# design.net
KiCad netlist of a schematic drawn in Altium Designer
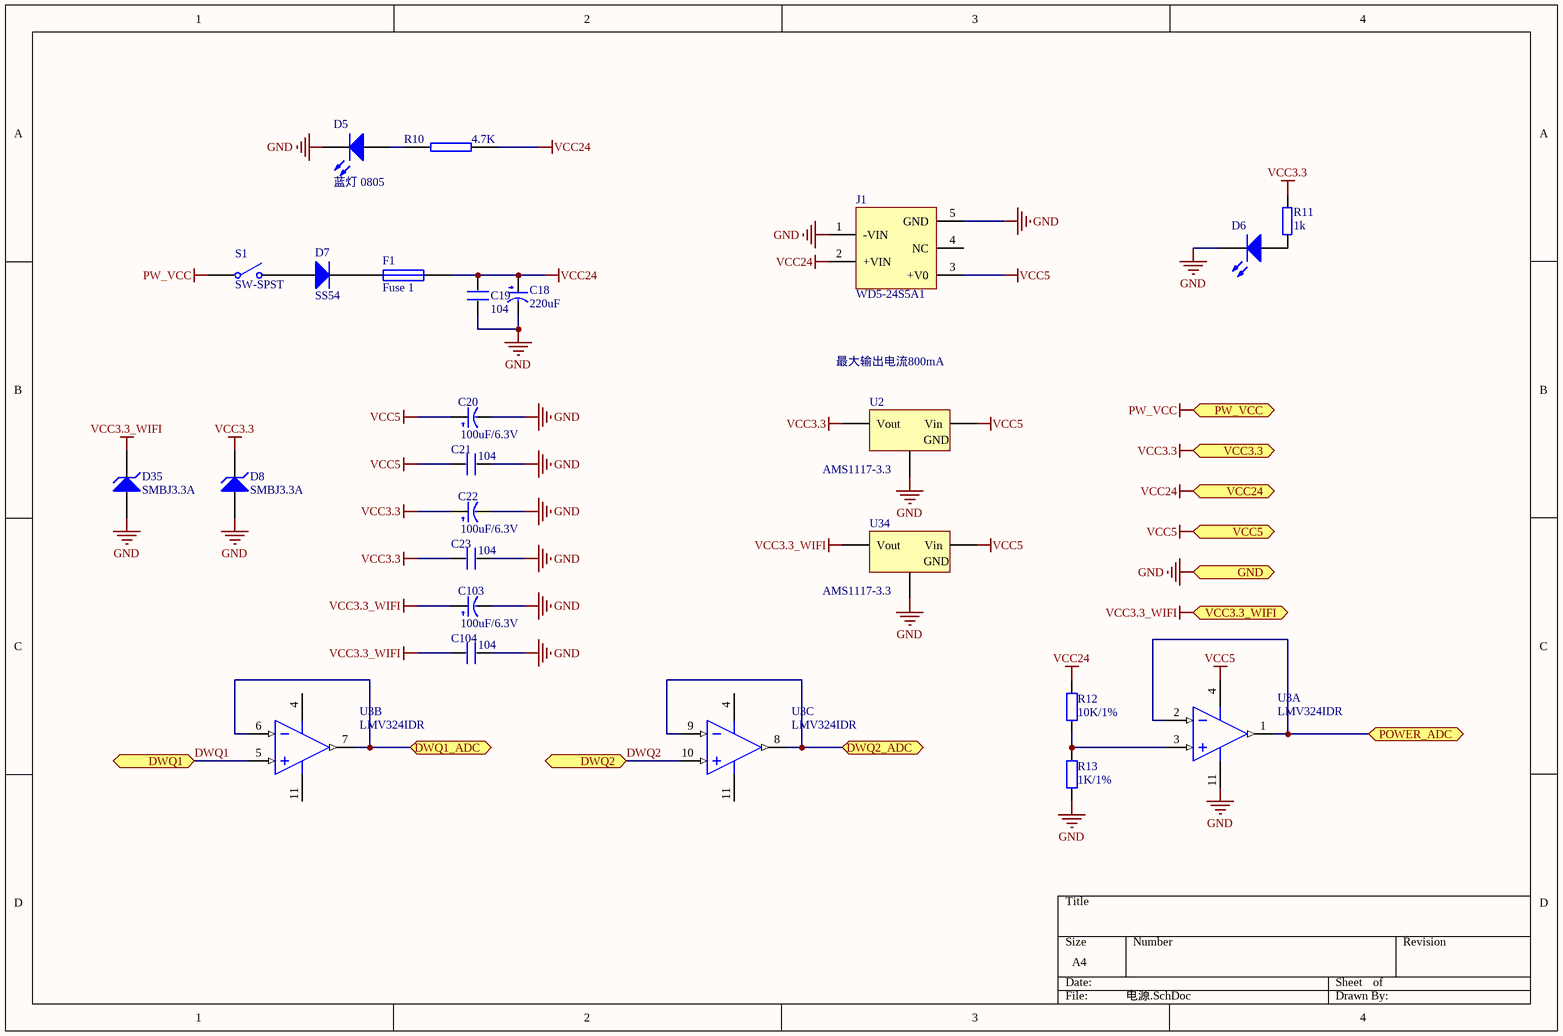
[diagram p0: 电源.SchDoc]

(export (version "E")
  (design (tool "Eeschema 10.0.6"))
  (components
    (comp (ref "C18") (value "220uF") (footprint "CC6.56.5") (libsource (lib "WarShip V3_SCH") (part "CAP")))
    (comp (ref "C19") (value "104") (footprint "0805_C") (libsource (lib "WarShip V3_SCH") (part "C")))
    (comp (ref "C20")
      (value "100uF/6.3V")
      (footprint "CASE-B_3528")
      (libsource (lib "WarShip V3_SCH") (part "CAP"))
    )
    (comp (ref "C21") (value "104") (footprint "0805_C") (libsource (lib "WarShip V3_SCH") (part "C")))
    (comp (ref "C22")
      (value "100uF/6.3V")
      (footprint "CASE-B_3528")
      (libsource (lib "WarShip V3_SCH") (part "CAP"))
    )
    (comp (ref "C23") (value "104") (footprint "0805_C") (libsource (lib "WarShip V3_SCH") (part "C")))
    (comp (ref "C103")
      (value "100uF/6.3V")
      (footprint "CASE-B_3528")
      (libsource (lib "WarShip V3_SCH") (part "CAP"))
    )
    (comp (ref "C104") (value "104") (footprint "0805_C") (libsource (lib "WarShip V3_SCH") (part "C")))
    (comp (ref "D5")
      (value "蓝灯 0805")
      (footprint "0805_LED_S1")
      (description "发光二极管")
      (libsource (lib "Miscellaneous Devices LC - 副本") (part "0805 蓝灯"))
    )
    (comp (ref "D6")
      (value "蓝灯 0805")
      (footprint "LC-0805_LED_S1")
      (description "Typical INFRARED GaAs LED")
      (fields (field (name "PUBLISHER") "Altium Limited"))
      (libsource (lib "继电器板_1") (part "LED0"))
    )
    (comp (ref "D7")
      (value "SS54")
      (footprint "SMA(DO-214AC)_S1")
      (description "二极管")
      (libsource (lib "Miscellaneous Devices LC") (part "SMA(DO-214AC) SS54"))
    )
    (comp (ref "D8")
      (value "SMBJ3.3A")
      (footprint "SMB(DO-214AA)_S1")
      (description "Zener Diode")
      (fields (field (name "PUBLISHER") "Altium Limited"))
      (libsource (lib "Miscellaneous Devices") (part "D Zener"))
    )
    (comp (ref "D35")
      (value "SMBJ3.3A")
      (footprint "SMB(DO-214AA)_S1")
      (description "Zener Diode")
      (fields (field (name "PUBLISHER") "Altium Limited"))
      (libsource (lib "Miscellaneous Devices") (part "D Zener"))
    )
    (comp (ref "F1")
      (value "Fuse 1")
      (footprint "1206")
      (description "Fuse")
      (fields (field (name "PUBLISHER") "Altium Limited"))
      (libsource (lib "Miscellaneous Devices") (part "Fuse 1"))
    )
    (comp (ref "J1")
      (value "WD5-24S5A1")
      (footprint "WD5-24S3V3")
      (libsource (lib "*") (part "WD5-24S3V3A1"))
    )
    (comp (ref "R10") (value "4.7K") (footprint "0603_R") (libsource (lib "*") (part "RES2")))
    (comp (ref "R11")
      (value "1k")
      (footprint "0805_R")
      (libsource (lib "Explorer STM32F407封装库") (part "R_2"))
    )
    (comp (ref "R12")
      (value "10K/1%")
      (footprint "0805_R")
      (description "Resistor")
      (fields (field (name "PUBLISHER") "Altium Limited"))
      (libsource (lib "Miscellaneous Devices") (part "Res2"))
    )
    (comp (ref "R13")
      (value "1K/1%")
      (footprint "0805_R")
      (description "Resistor")
      (fields (field (name "PUBLISHER") "Altium Limited"))
      (libsource (lib "Miscellaneous Devices") (part "Res2"))
    )
    (comp (ref "S1")
      (value "SW-SPST")
      (footprint "SPST-2")
      (description "Single-Pole, Single-Throw Switch")
      (fields (field (name "PUBLISHER") "Altium Limited"))
      (libsource (lib "Miscellaneous Devices") (part "SW-SPST"))
    )
    (comp (ref "U2")
      (value "AMS1117-3.3")
      (footprint "SOT-223")
      (description "低压差线性稳压(LDO)")
      (libsource (lib "Miscellaneous Devices LC") (part "SOT-223 AMS1117-3.3"))
    )
    (comp (ref "U3")
      (value "LMV324IDR")
      (footprint "SOIC-14_150mil")
      (description "运放")
      (libsource (lib "Miscellaneous Devices LC") (part "LMV324IDR"))
    )
    (comp (ref "U34")
      (value "AMS1117-3.3")
      (footprint "SOT-223")
      (description "低压差线性稳压(LDO)")
      (libsource (lib "Miscellaneous Devices LC") (part "SOT-223 AMS1117-3.3"))
    )
  )
  (nets
    (net (code "1") (name "/DWQ1") (class "Default")
      (node (ref "U3") (pin "5") (pinfunction "INB+_5") (pintype "input"))
    )
    (net (code "2") (name "/DWQ1_ADC") (class "Default")
      (node (ref "U3") (pin "6") (pinfunction "INB-_6") (pintype "input"))
      (node (ref "U3") (pin "7") (pinfunction "OUTB_7") (pintype "output"))
    )
    (net (code "3") (name "/DWQ2") (class "Default")
      (node (ref "U3") (pin "10") (pinfunction "INC+_10") (pintype "input"))
    )
    (net (code "4") (name "/DWQ2_ADC") (class "Default")
      (node (ref "U3") (pin "8") (pinfunction "OUTC_8") (pintype "output"))
      (node (ref "U3") (pin "9") (pinfunction "INC-_9") (pintype "input"))
    )
    (net (code "5") (name "/POWER_ADC") (class "Default")
      (node (ref "U3") (pin "1") (pinfunction "OUTA_1") (pintype "output"))
      (node (ref "U3") (pin "2") (pinfunction "INA-_2") (pintype "input"))
    )
    (net (code "6") (name "GND") (class "Default")
      (node (ref "C103") (pin "2") (pinfunction "GND_2") (pintype "passive"))
      (node (ref "C104") (pin "1") (pintype "passive"))
      (node (ref "C18") (pin "2") (pinfunction "GND_2") (pintype "passive"))
      (node (ref "C19") (pin "2") (pintype "passive"))
      (node (ref "C20") (pin "2") (pinfunction "GND_2") (pintype "passive"))
      (node (ref "C21") (pin "1") (pintype "passive"))
      (node (ref "C22") (pin "2") (pinfunction "GND_2") (pintype "passive"))
      (node (ref "C23") (pin "1") (pintype "passive"))
      (node (ref "D35") (pin "1") (pinfunction "A_1") (pintype "passive"))
      (node (ref "D5") (pin "K") (pinfunction "K_K") (pintype "passive"))
      (node (ref "D6") (pin "K") (pinfunction "K_K") (pintype "passive"))
      (node (ref "D8") (pin "1") (pinfunction "A_1") (pintype "passive"))
      (node (ref "J1") (pin "1") (pinfunction "-VIN_1") (pintype "passive"))
      (node (ref "J1") (pin "5") (pinfunction "GND_5") (pintype "passive"))
      (node (ref "R13") (pin "1") (pinfunction "1_1") (pintype "passive"))
      (node (ref "U2") (pin "1") (pinfunction "GND_1") (pintype "passive"))
      (node (ref "U3") (pin "11") (pinfunction "V-_11") (pintype "power_in"))
      (node (ref "U34") (pin "1") (pinfunction "GND_1") (pintype "passive"))
    )
    (net (code "7") (name "Net-(D5-PadA)") (class "Default")
      (node (ref "D5") (pin "A") (pinfunction "A_A") (pintype "passive"))
      (node (ref "R10") (pin "2") (pinfunction "2_2") (pintype "passive"))
    )
    (net (code "8") (name "Net-(D6-PadA)") (class "Default")
      (node (ref "D6") (pin "A") (pinfunction "A_A") (pintype "passive"))
      (node (ref "R11") (pin "2") (pintype "passive"))
    )
    (net (code "9") (name "Net-(D7-A)") (class "Default")
      (node (ref "D7") (pin "1") (pinfunction "A_1") (pintype "passive"))
      (node (ref "S1") (pin "2") (pinfunction "NO_2") (pintype "passive"))
    )
    (net (code "10") (name "Net-(D7-K)") (class "Default")
      (node (ref "D7") (pin "2") (pinfunction "K_2") (pintype "passive"))
      (node (ref "F1") (pin "1") (pinfunction "1_1") (pintype "passive"))
    )
    (net (code "11") (name "Net-(U3A-INA+)") (class "Default")
      (node (ref "R12") (pin "1") (pinfunction "1_1") (pintype "passive"))
      (node (ref "R13") (pin "2") (pinfunction "2_2") (pintype "passive"))
      (node (ref "U3") (pin "3") (pinfunction "INA+_3") (pintype "input"))
    )
    (net (code "12") (name "PW_VCC") (class "Default")
      (node (ref "S1") (pin "1") (pinfunction "COMMON_1") (pintype "passive"))
    )
    (net (code "13") (name "VCC3.3") (class "Default")
      (node (ref "C22") (pin "1") (pinfunction "VCC_1") (pintype "passive"))
      (node (ref "C23") (pin "2") (pintype "passive"))
      (node (ref "D8") (pin "2") (pinfunction "K_2") (pintype "passive"))
      (node (ref "R11") (pin "1") (pintype "passive"))
      (node (ref "U2") (pin "2") (pinfunction "Vout_2") (pintype "passive"))
    )
    (net (code "14") (name "VCC3.3_WIFI") (class "Default")
      (node (ref "C103") (pin "1") (pinfunction "VCC_1") (pintype "passive"))
      (node (ref "C104") (pin "2") (pintype "passive"))
      (node (ref "D35") (pin "2") (pinfunction "K_2") (pintype "passive"))
      (node (ref "U34") (pin "2") (pinfunction "Vout_2") (pintype "passive"))
    )
    (net (code "15") (name "VCC5") (class "Default")
      (node (ref "C20") (pin "1") (pinfunction "VCC_1") (pintype "passive"))
      (node (ref "C21") (pin "2") (pintype "passive"))
      (node (ref "J1") (pin "3") (pinfunction "+V0_3") (pintype "passive"))
      (node (ref "U2") (pin "3") (pinfunction "Vin_3") (pintype "passive"))
      (node (ref "U3") (pin "4") (pinfunction "V+_4") (pintype "power_in"))
      (node (ref "U34") (pin "3") (pinfunction "Vin_3") (pintype "passive"))
    )
    (net (code "16") (name "VCC24") (class "Default")
      (node (ref "C18") (pin "1") (pinfunction "VCC_1") (pintype "passive"))
      (node (ref "C19") (pin "1") (pintype "passive"))
      (node (ref "F1") (pin "2") (pinfunction "2_2") (pintype "passive"))
      (node (ref "J1") (pin "2") (pinfunction "+VIN_2") (pintype "passive"))
      (node (ref "R10") (pin "1") (pinfunction "1_1") (pintype "passive"))
      (node (ref "R12") (pin "2") (pinfunction "2_2") (pintype "passive"))
    )
    (net (code "17") (name "unconnected-(J1-NC-Pad4)") (class "Default")
      (node (ref "J1") (pin "4") (pinfunction "NC_4") (pintype "passive"))
    )
    (net (code "18") (name "unconnected-(U3B-V+-Pad4)") (class "Default")
      (node (ref "U3") (pin "4") (pinfunction "V+_4") (pintype "power_in"))
    )
    (net (code "19") (name "unconnected-(U3B-V--Pad11)") (class "Default")
      (node (ref "U3") (pin "11") (pinfunction "V-_11") (pintype "power_in"))
    )
    (net (code "20") (name "unconnected-(U3C-V+-Pad4)") (class "Default")
      (node (ref "U3") (pin "4") (pinfunction "V+_4") (pintype "power_in"))
    )
    (net (code "21") (name "unconnected-(U3C-V--Pad11)") (class "Default")
      (node (ref "U3") (pin "11") (pinfunction "V-_11") (pintype "power_in"))
    )
  )
)
